# mcat-4cu-v2.net
KiCad netlist of a schematic drawn in EAGLE
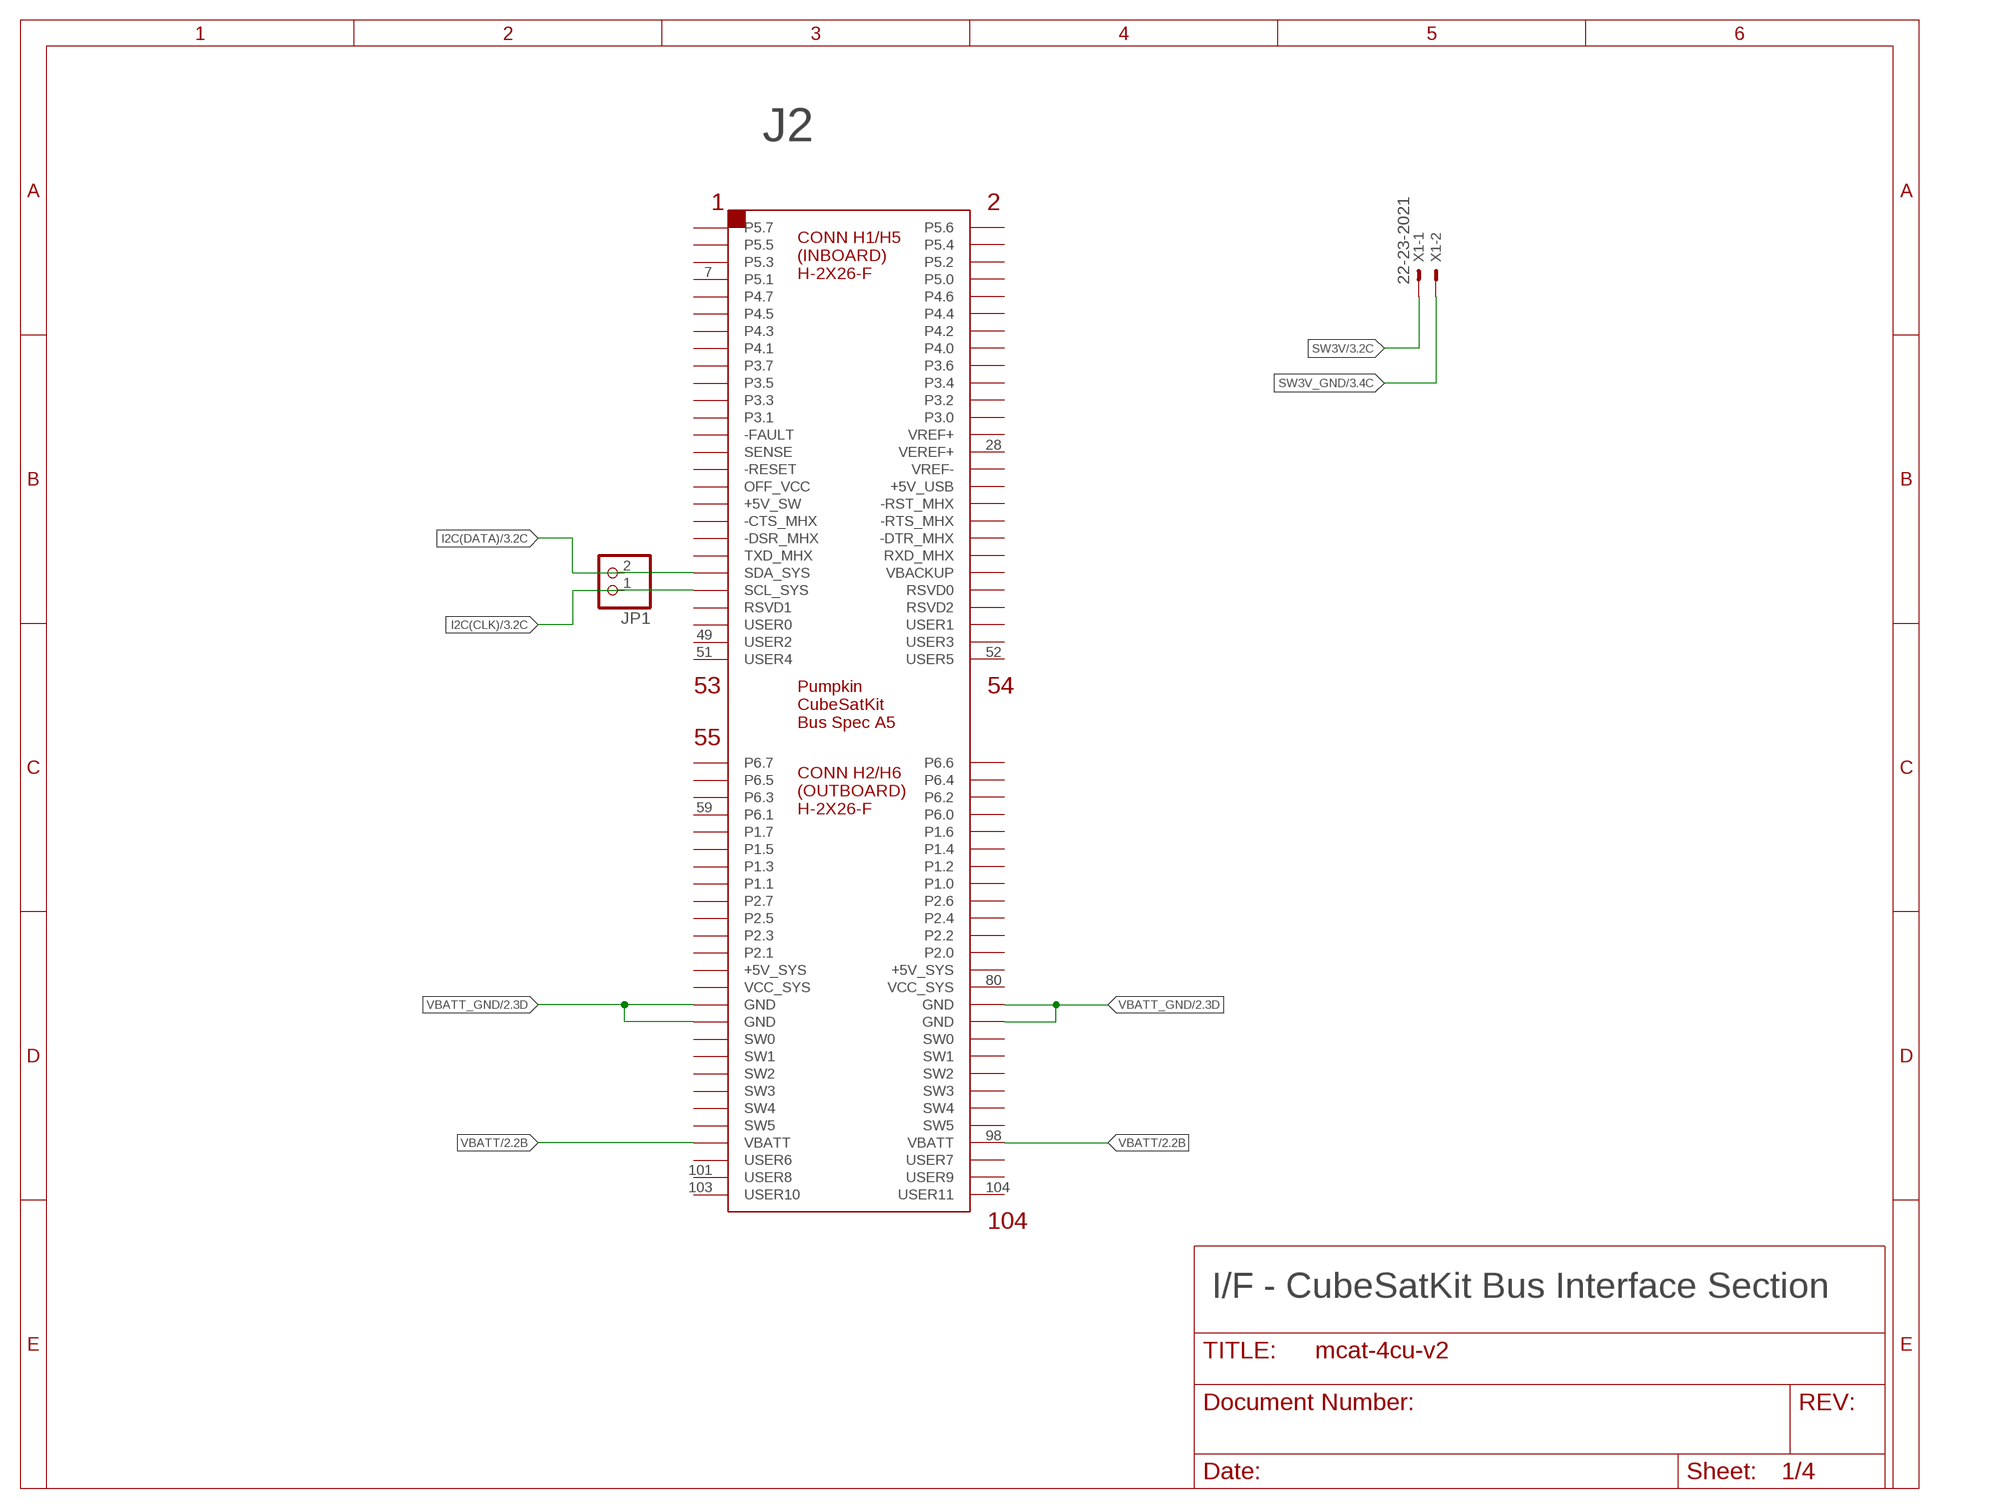
[diagram p0: schematic, sheet 1]
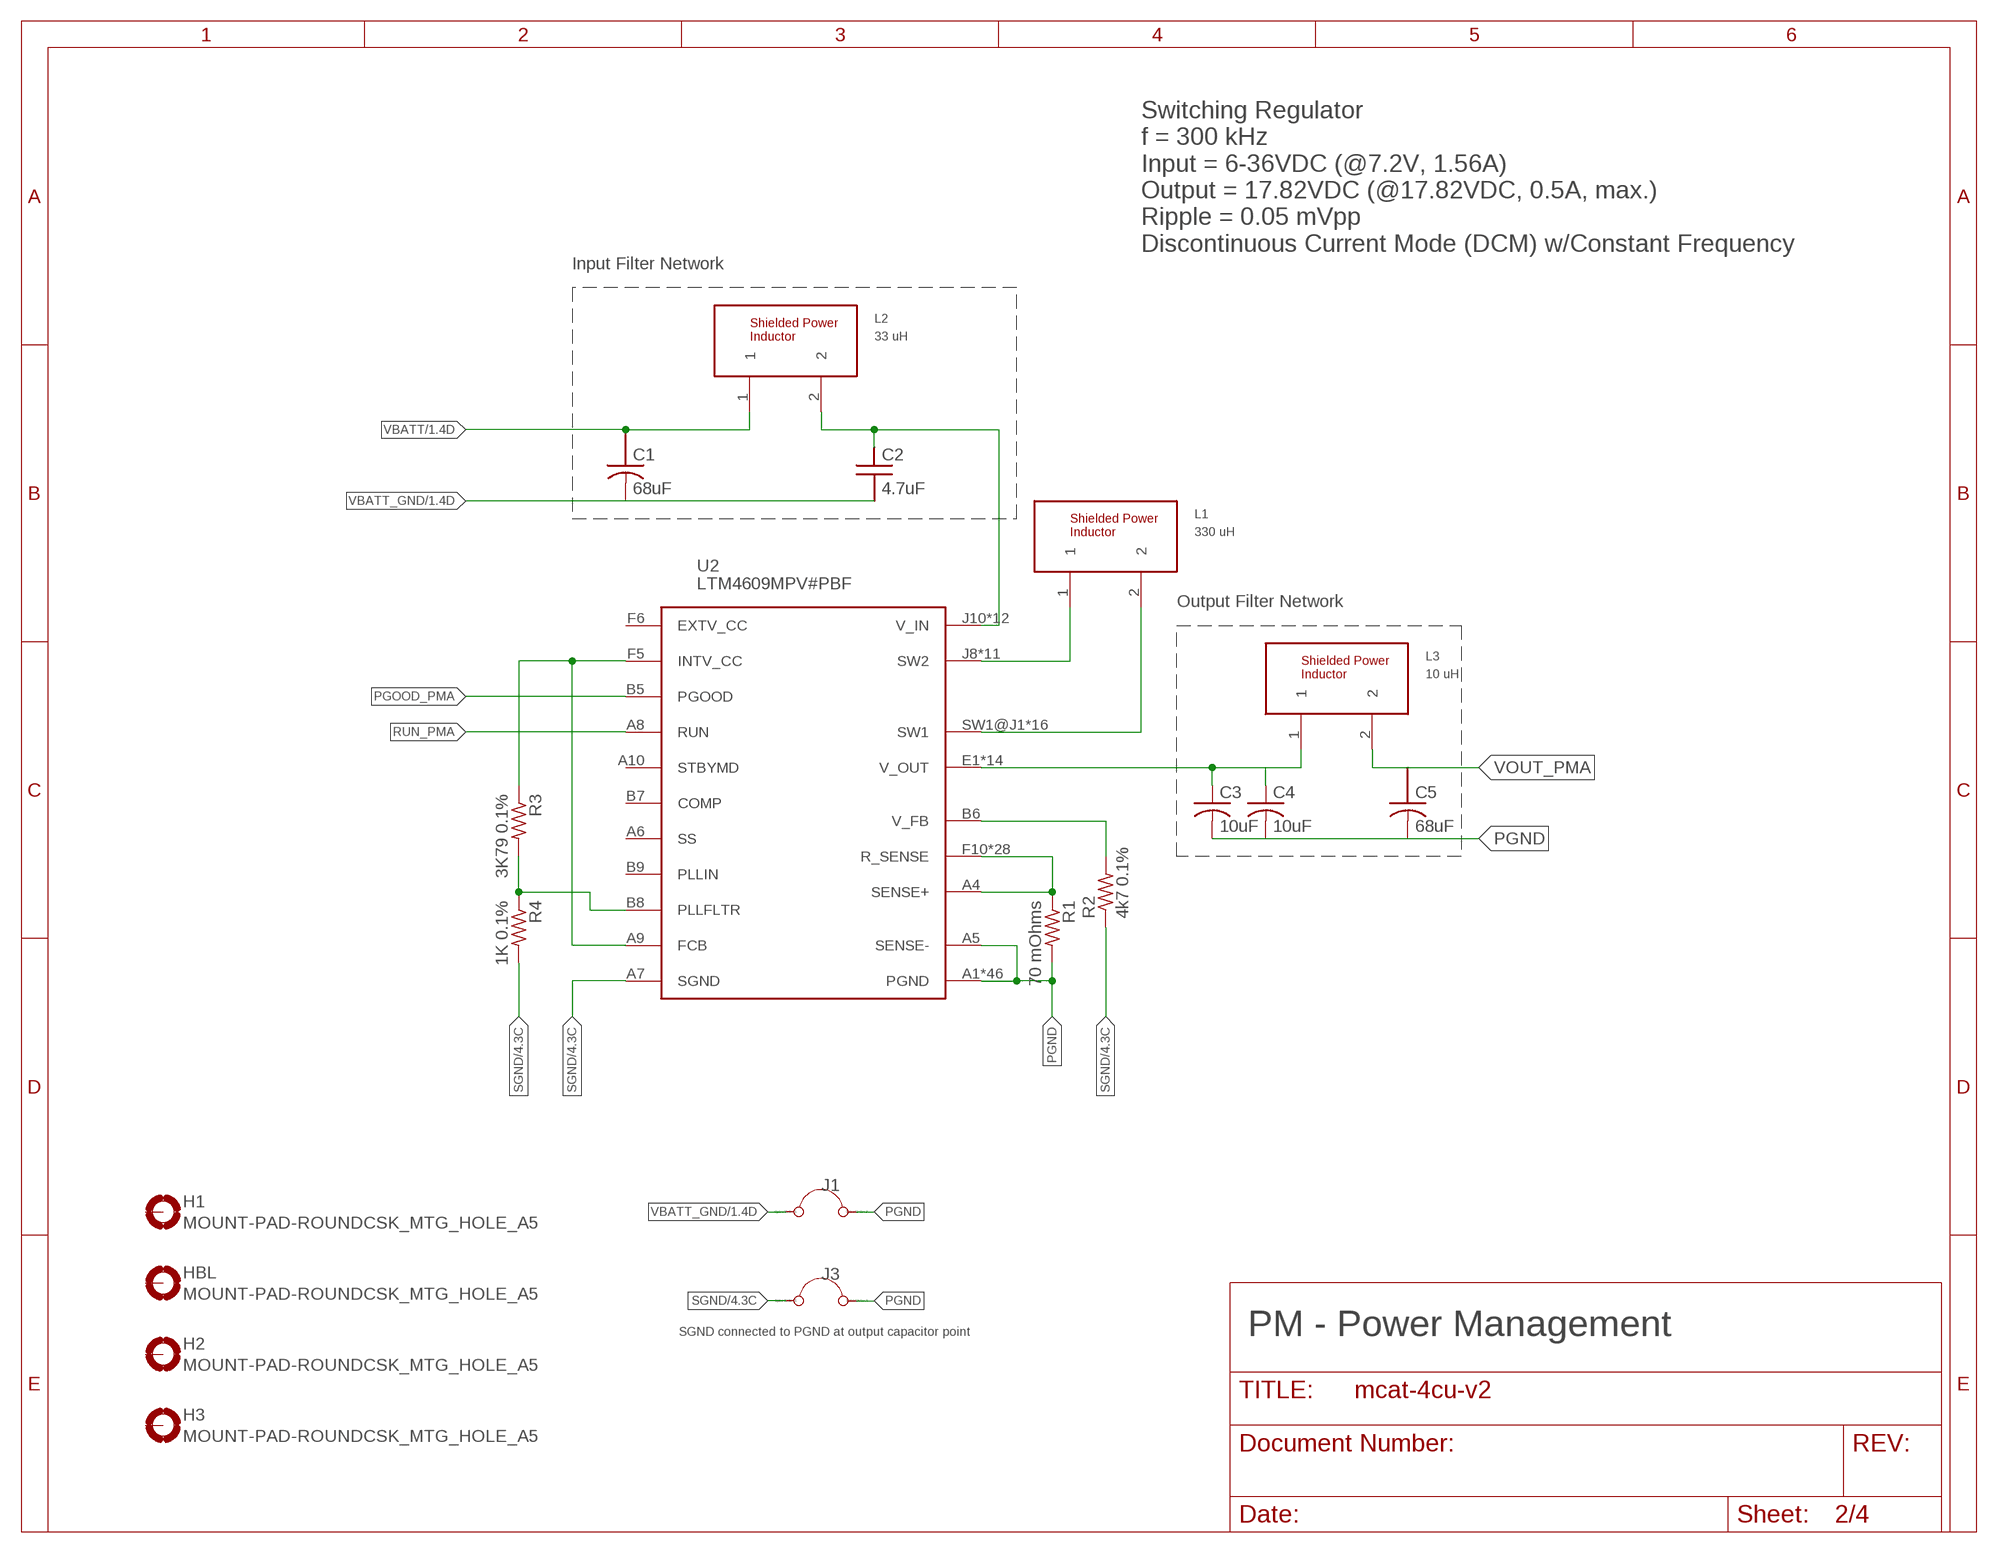
[diagram p1: schematic, sheet 2]
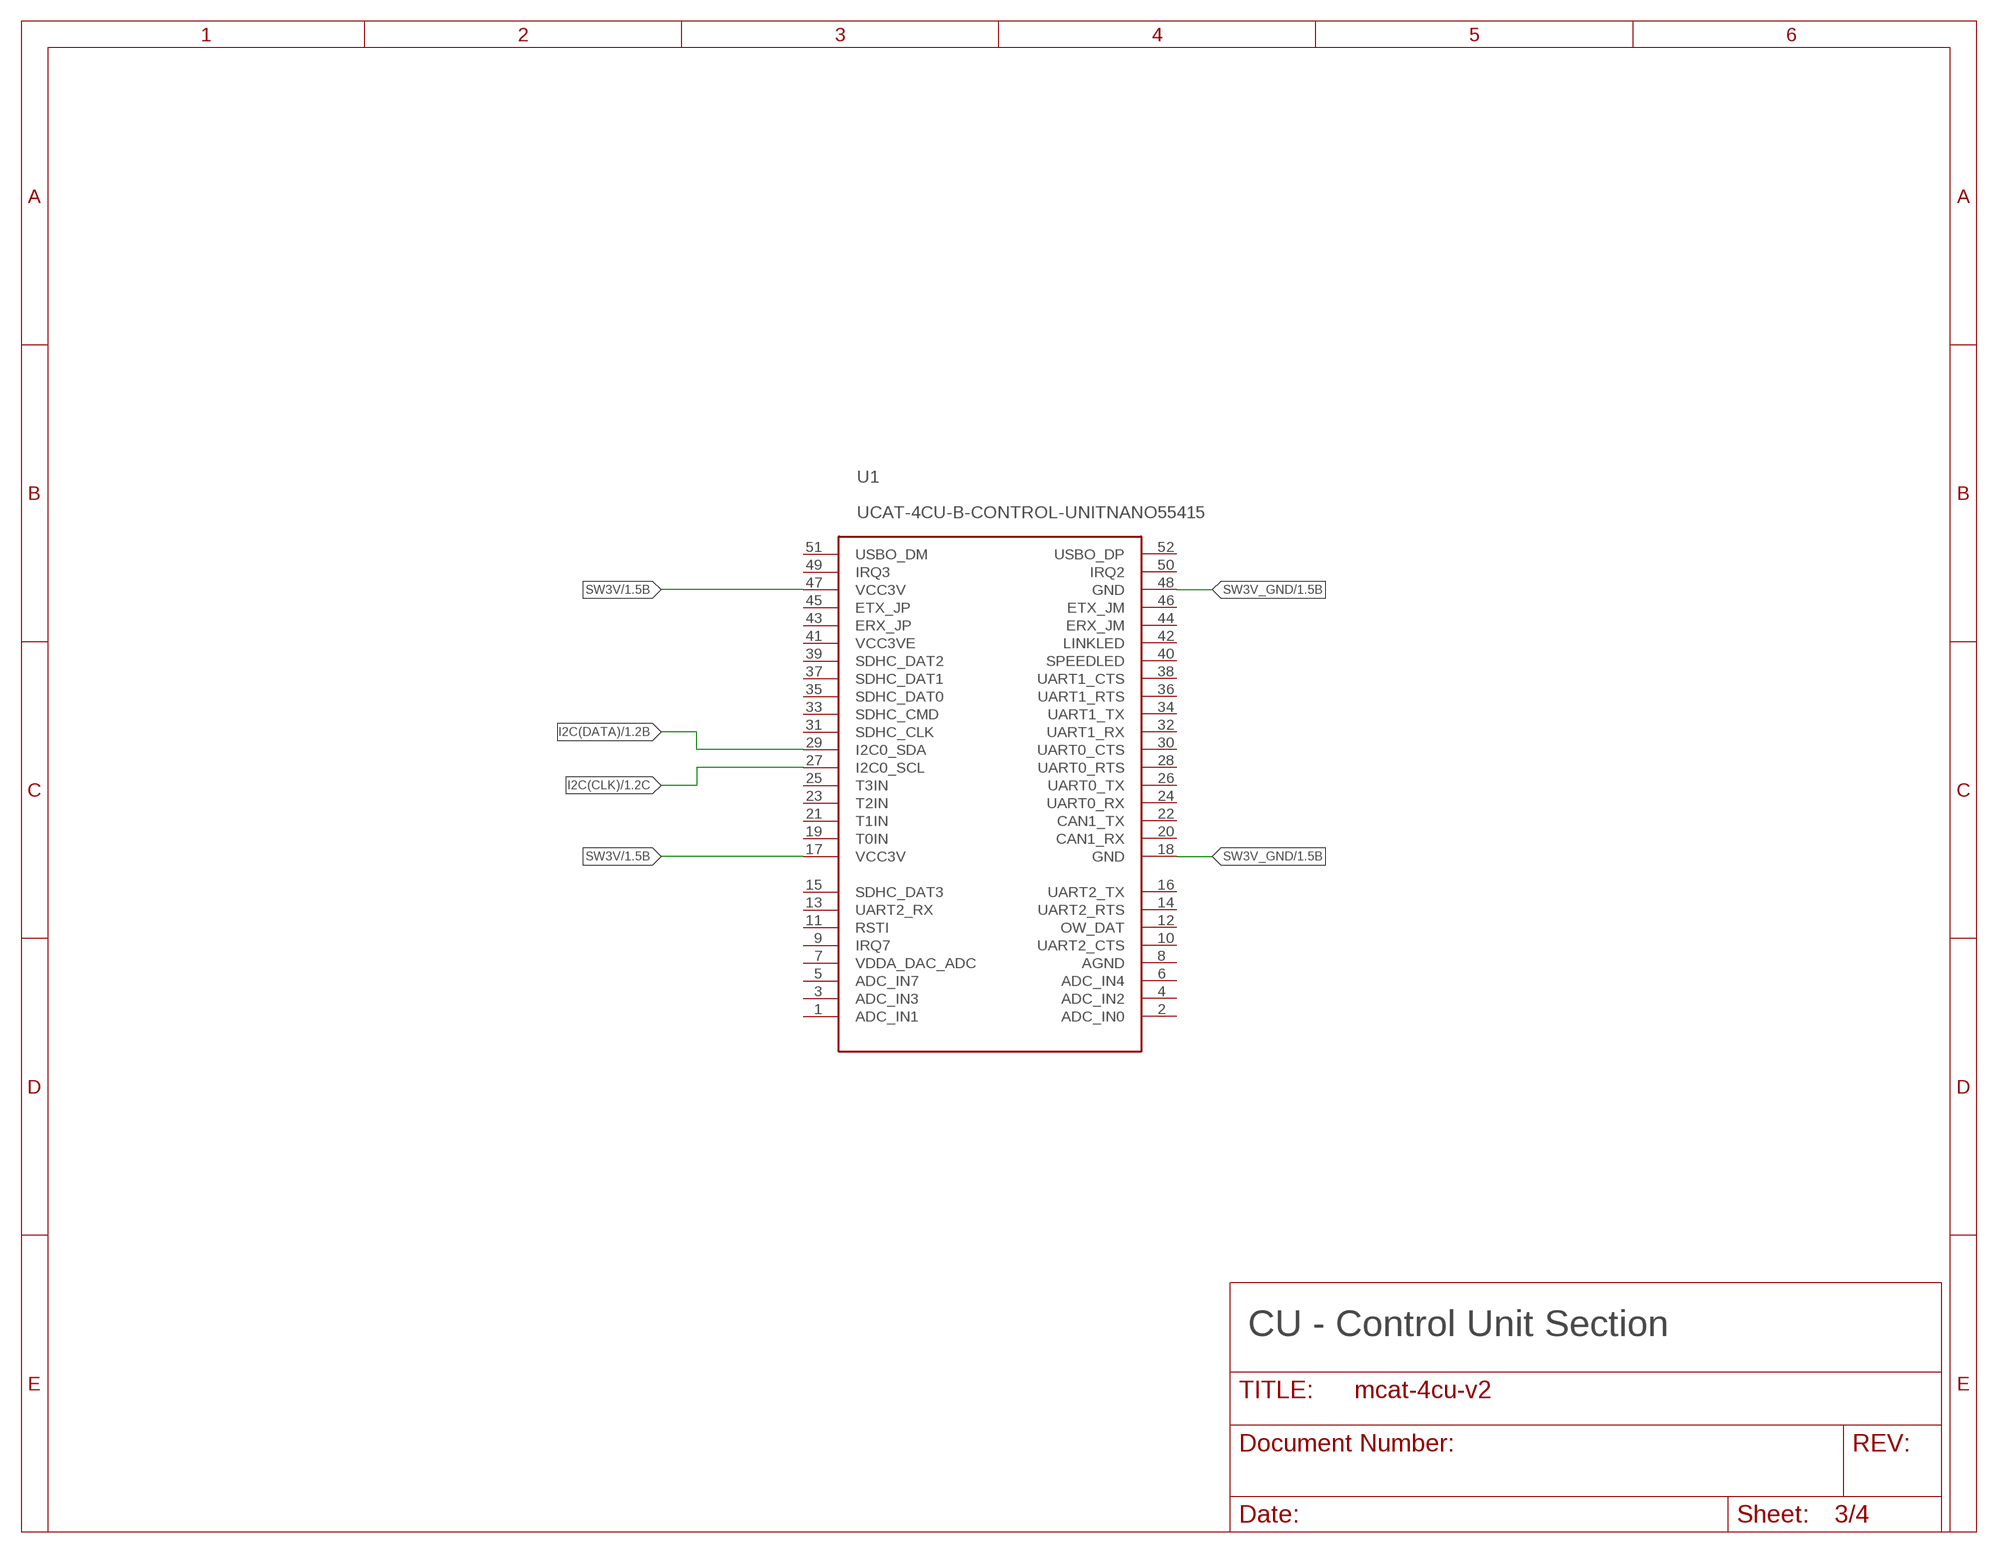
[diagram p2: schematic, sheet 3]
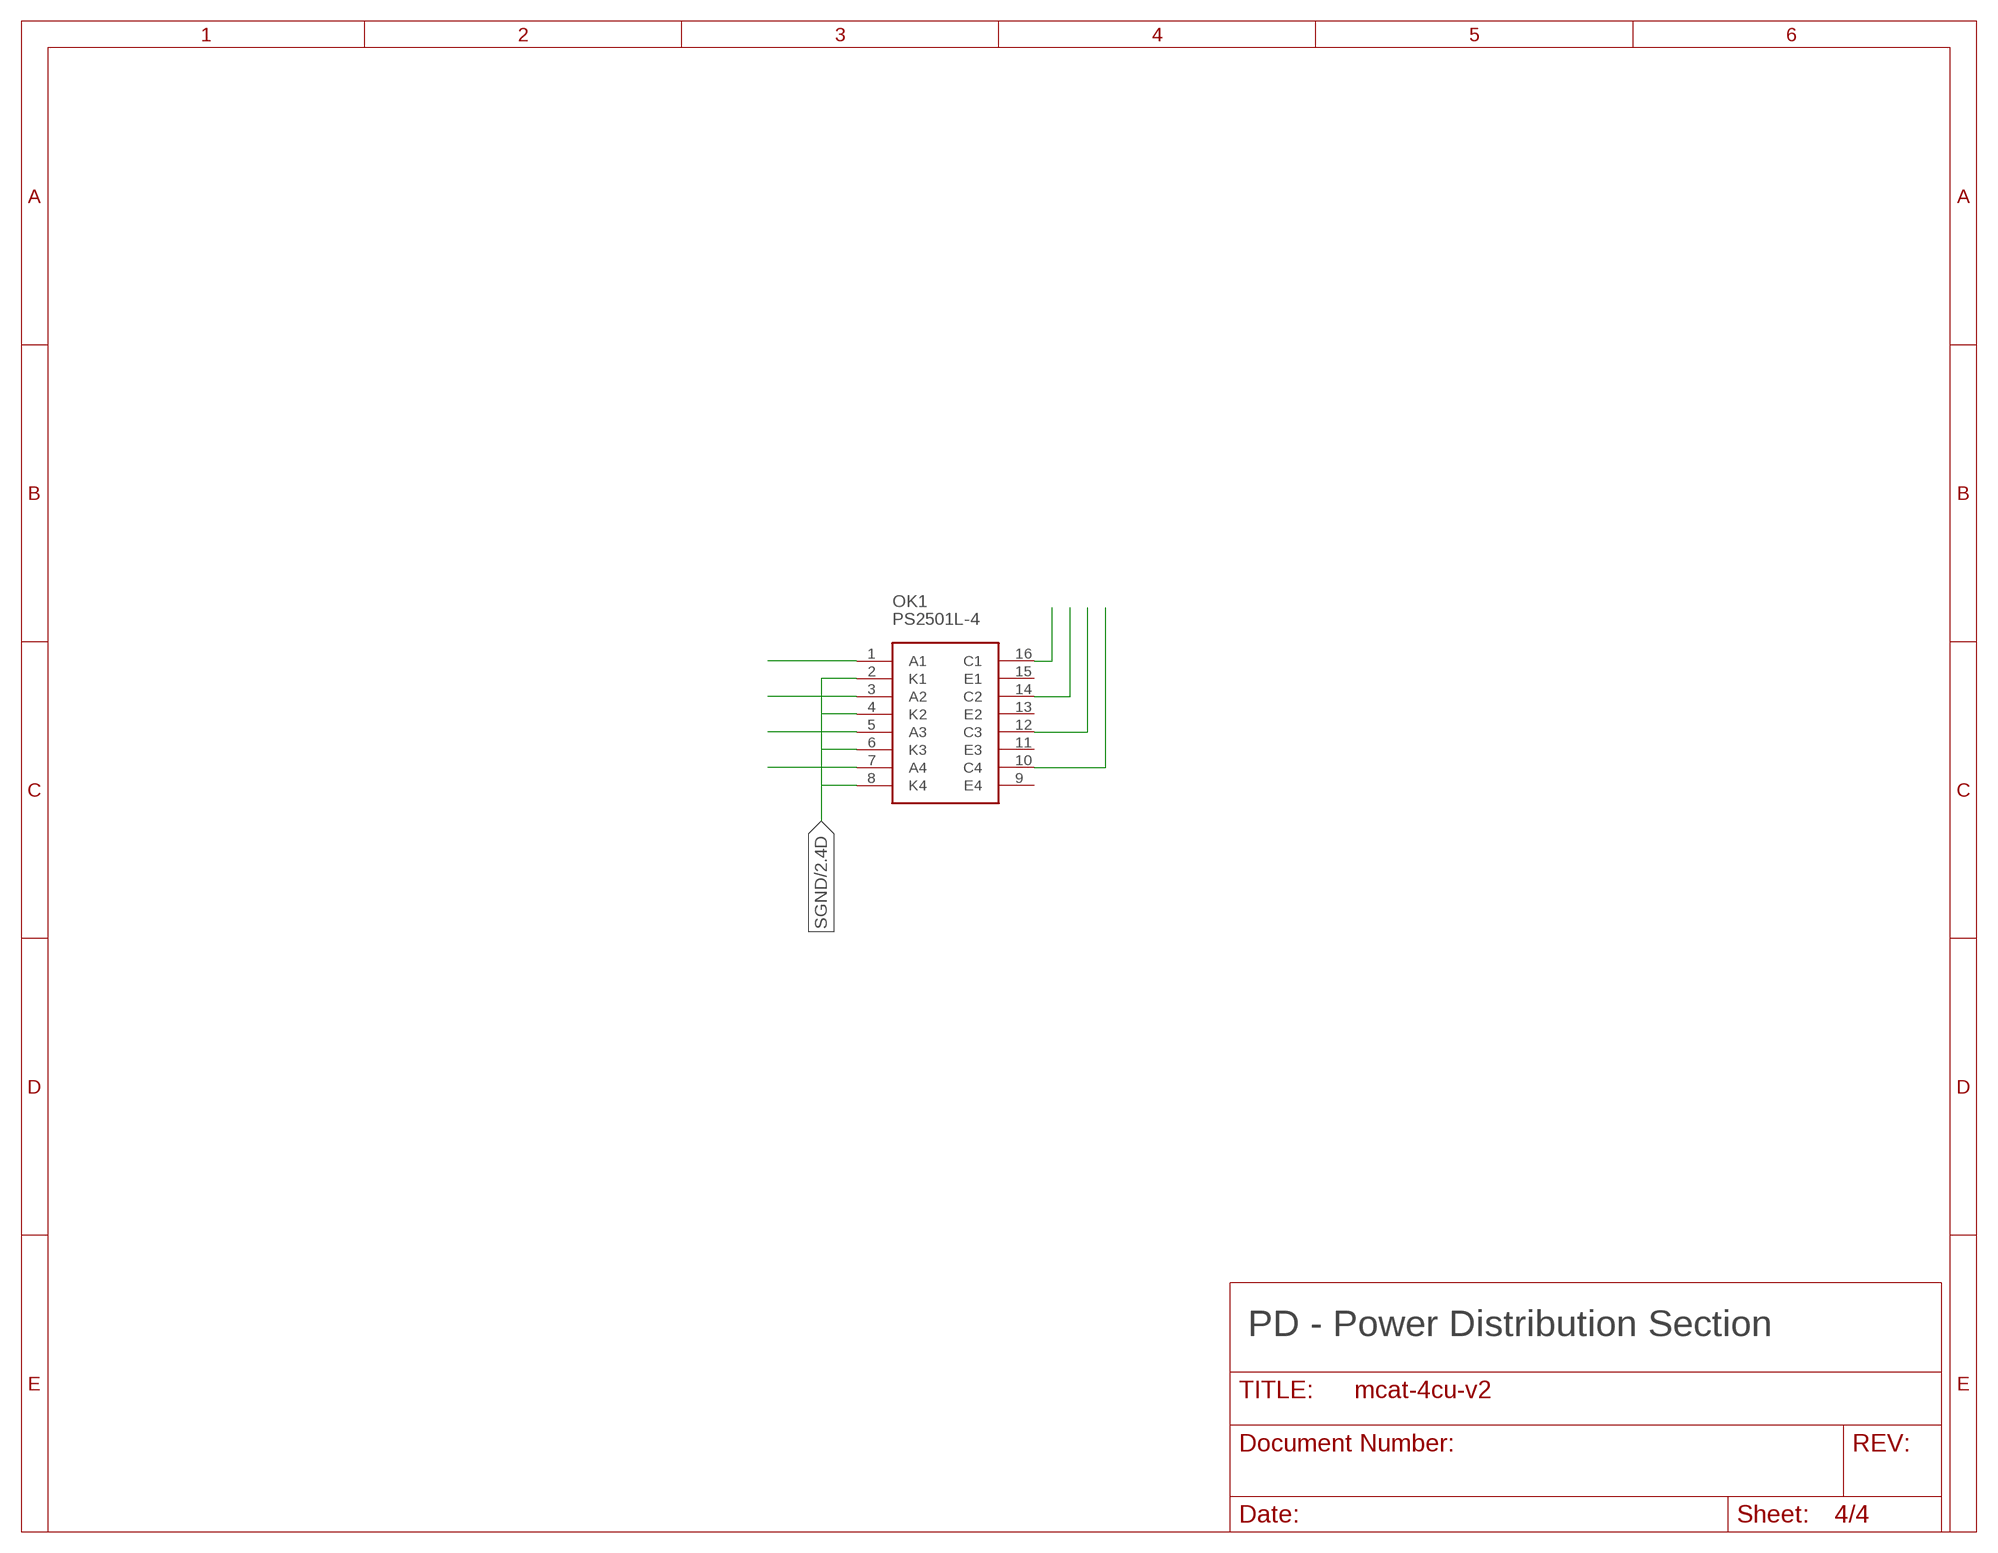
[diagram p3: schematic, sheet 4]

(export (version "E")
  (design (tool "Eeschema 10.0.6"))
  (components
    (comp (ref "J2")
      (value "CSK-BUS-CONN2X2X26")
      (footprint "eagle-import:CSK-BUS-PKG")
      (libsource (lib "eagle-import") (part "CSK-BUS-CONN2X2X26"))
    )
    (comp (ref "JP1")
      (value "PINHD-1X2")
      (footprint "eagle-import:1X02")
      (libsource (lib "eagle-import") (part "PINHD-1X2"))
    )
    (comp (ref "X1")
      (value "22-23-2021")
      (footprint "eagle-import:22-23-2021")
      (fields (field (name "MF") "MOLEX"))
      (libsource (lib "eagle-import") (part "22-23-2021"))
    )
    (comp (ref "OK1")
      (value "PS2501L-4")
      (footprint "eagle-import:PS2501L-4")
      (libsource (lib "eagle-import") (part "PS2501L-4"))
    )
    (comp (ref "C1")
      (value "68uF")
      (footprint "eagle-import:OS-CON-SVPF-F12")
      (libsource (lib "eagle-import") (part "OSCON-50SVPF68M"))
    )
    (comp (ref "C2")
      (value "4.7uF")
      (footprint "eagle-import:MLCC-X7R-1210")
      (libsource (lib "eagle-import") (part "AVX-LD105C475KAB2A"))
    )
    (comp (ref "C3")
      (value "10uF")
      (footprint "eagle-import:C1210K")
      (libsource (lib "eagle-import") (part "C-USC1210K"))
    )
    (comp (ref "C4")
      (value "10uF")
      (footprint "eagle-import:C1210K")
      (libsource (lib "eagle-import") (part "C-USC1210K"))
    )
    (comp (ref "C5")
      (value "68uF")
      (footprint "eagle-import:OS-CON-SVPF-F12")
      (libsource (lib "eagle-import") (part "OSCON-50SVPF68M"))
    )
    (comp (ref "H1")
      (value "MOUNT-PAD-ROUNDCSK_MTG_HOLE_A5")
      (footprint "eagle-import:CSK_MOUNTING_HOLE")
      (libsource (lib "eagle-import") (part "MOUNT-PAD-ROUNDCSK_MTG_HOLE_A5"))
    )
    (comp (ref "H2")
      (value "MOUNT-PAD-ROUNDCSK_MTG_HOLE_A5")
      (footprint "eagle-import:CSK_MOUNTING_HOLE")
      (libsource (lib "eagle-import") (part "MOUNT-PAD-ROUNDCSK_MTG_HOLE_A5"))
    )
    (comp (ref "H3")
      (value "MOUNT-PAD-ROUNDCSK_MTG_HOLE_A5")
      (footprint "eagle-import:CSK_MOUNTING_HOLE")
      (libsource (lib "eagle-import") (part "MOUNT-PAD-ROUNDCSK_MTG_HOLE_A5"))
    )
    (comp (ref "HBL")
      (value "MOUNT-PAD-ROUNDCSK_MTG_HOLE_A5")
      (footprint "eagle-import:CSK_MOUNTING_HOLE")
      (libsource (lib "eagle-import") (part "MOUNT-PAD-ROUNDCSK_MTG_HOLE_A5"))
    )
    (comp (ref "J1")
      (value "JUMPER")
      (footprint "eagle-import:05")
      (libsource (lib "eagle-import") (part "JUMPER"))
    )
    (comp (ref "J3")
      (value "JUMPER")
      (footprint "eagle-import:05")
      (libsource (lib "eagle-import") (part "JUMPER"))
    )
    (comp (ref "L1")
      (value "330 uH")
      (footprint "eagle-import:MSS1048")
      (libsource (lib "eagle-import") (part "MSS1048-334KL_"))
    )
    (comp (ref "L2")
      (value "33 uH")
      (footprint "eagle-import:MSS1048")
      (libsource (lib "eagle-import") (part "MSS1038-333ML_"))
    )
    (comp (ref "L3")
      (value "10 uH")
      (footprint "eagle-import:SERIES-POWER-INDUCTORS")
      (fields (field (name "MF") "PANASONIC") (field (name "MPN") "ELL5PS100M"))
      (libsource (lib "eagle-import") (part "ELL-5PS100M"))
    )
    (comp (ref "R1")
      (value "70 mOhms")
      (footprint "eagle-import:R1206")
      (libsource (lib "eagle-import") (part "resistor_R-US_R1206"))
    )
    (comp (ref "R2")
      (value "4k7 0.1%")
      (footprint "eagle-import:R0603")
      (libsource (lib "eagle-import") (part "resistor_R-US_R0603"))
    )
    (comp (ref "R3")
      (value "3K79 0.1%")
      (footprint "eagle-import:R0805")
      (libsource (lib "eagle-import") (part "R-US_R0805"))
    )
    (comp (ref "R4")
      (value "1K 0.1%")
      (footprint "eagle-import:R0805")
      (libsource (lib "eagle-import") (part "R-US_R0805"))
    )
    (comp (ref "U2")
      (value "LTM4609MPV#PBF")
      (footprint "eagle-import:LGA-141-LTC-05-08-1840-B")
      (libsource (lib "eagle-import") (part "LTM4609MPV#PBFROHS/HITEMP"))
    )
    (comp (ref "U1")
      (value "UCAT-4CU-B-CONTROL-UNITNANO55415")
      (footprint "eagle-import:MOLEX-MINI-PCI-EXPRESS-8MM-52CKT")
      (libsource (lib "eagle-import") (part "UCAT-4CU-B-CONTROL-UNITNANO55415"))
    )
  )
  (nets
    (net (code "1") (name "I2C(CLK)") (class "Default")
      (node (ref "J2") (pin "43") (pinfunction "SCL_SYS_43") (pintype "bidirectional"))
      (node (ref "JP1") (pin "1") (pinfunction "1_1") (pintype "passive"))
      (node (ref "U1") (pin "27") (pinfunction "I2C0_SCL_27") (pintype "bidirectional"))
    )
    (net (code "2") (name "I2C(DATA)") (class "Default")
      (node (ref "J2") (pin "41") (pinfunction "SDA_SYS_41") (pintype "bidirectional"))
      (node (ref "JP1") (pin "2") (pinfunction "2_2") (pintype "passive"))
      (node (ref "U1") (pin "29") (pinfunction "I2C0_SDA_29") (pintype "bidirectional"))
    )
    (net (code "3") (name "Net-(C2-Pad1)") (class "Default")
      (node (ref "C2") (pin "1") (pinfunction "1_1") (pintype "passive"))
      (node (ref "L2") (pin "2") (pinfunction "2_2") (pintype "bidirectional"))
      (node (ref "U2") (pin "J10") (pinfunction "V_IN_J10") (pintype "bidirectional"))
      (node (ref "U2") (pin "J11") (pinfunction "V_IN_J11") (pintype "bidirectional"))
      (node (ref "U2") (pin "J12") (pinfunction "V_IN_J12") (pintype "bidirectional"))
      (node (ref "U2") (pin "K10") (pinfunction "V_IN_K10") (pintype "bidirectional"))
      (node (ref "U2") (pin "K11") (pinfunction "V_IN_K11") (pintype "bidirectional"))
      (node (ref "U2") (pin "K12") (pinfunction "V_IN_K12") (pintype "bidirectional"))
      (node (ref "U2") (pin "L10") (pinfunction "V_IN_L10") (pintype "bidirectional"))
      (node (ref "U2") (pin "L11") (pinfunction "V_IN_L11") (pintype "bidirectional"))
      (node (ref "U2") (pin "L12") (pinfunction "V_IN_L12") (pintype "bidirectional"))
      (node (ref "U2") (pin "M10") (pinfunction "V_IN_M10") (pintype "bidirectional"))
      (node (ref "U2") (pin "M11") (pinfunction "V_IN_M11") (pintype "bidirectional"))
      (node (ref "U2") (pin "M12") (pinfunction "V_IN_M12") (pintype "bidirectional"))
    )
    (net (code "4") (name "Net-(C3-Pad1)") (class "Default")
      (node (ref "C3") (pin "1") (pinfunction "1_1") (pintype "passive"))
      (node (ref "C4") (pin "1") (pinfunction "1_1") (pintype "passive"))
      (node (ref "L3") (pin "1") (pinfunction "1_1") (pintype "bidirectional"))
      (node (ref "U2") (pin "E1") (pinfunction "V_OUT_E1") (pintype "bidirectional"))
      (node (ref "U2") (pin "E2") (pinfunction "V_OUT_E2") (pintype "bidirectional"))
      (node (ref "U2") (pin "F1") (pinfunction "V_OUT_F1") (pintype "bidirectional"))
      (node (ref "U2") (pin "F2") (pinfunction "V_OUT_F2") (pintype "bidirectional"))
      (node (ref "U2") (pin "F3") (pinfunction "V_OUT_F3") (pintype "bidirectional"))
      (node (ref "U2") (pin "F4") (pinfunction "V_OUT_F4") (pintype "bidirectional"))
      (node (ref "U2") (pin "G1") (pinfunction "V_OUT_G1") (pintype "bidirectional"))
      (node (ref "U2") (pin "G2") (pinfunction "V_OUT_G2") (pintype "bidirectional"))
      (node (ref "U2") (pin "G3") (pinfunction "V_OUT_G3") (pintype "bidirectional"))
      (node (ref "U2") (pin "G4") (pinfunction "V_OUT_G4") (pintype "bidirectional"))
      (node (ref "U2") (pin "H2") (pinfunction "V_OUT_H2") (pintype "bidirectional"))
      (node (ref "U2") (pin "H3") (pinfunction "V_OUT_H3") (pintype "bidirectional"))
      (node (ref "U2") (pin "H4") (pinfunction "V_OUT_H4") (pintype "bidirectional"))
      (node (ref "U2") (pin "VOUT") (pinfunction "V_OUT_VOUT") (pintype "bidirectional"))
    )
    (net (code "5") (name "Net-(J2-GND-Pad82)") (class "Default")
      (node (ref "J2") (pin "82") (pinfunction "GND_82") (pintype "bidirectional"))
      (node (ref "J2") (pin "84") (pinfunction "GND_84") (pintype "bidirectional"))
    )
    (net (code "6") (name "Net-(L1-Pad1)") (class "Default")
      (node (ref "L1") (pin "1") (pinfunction "1_1") (pintype "bidirectional"))
      (node (ref "U2") (pin "J8") (pinfunction "SW2_J8") (pintype "bidirectional"))
      (node (ref "U2") (pin "J9") (pinfunction "SW2_J9") (pintype "bidirectional"))
      (node (ref "U2") (pin "K7") (pinfunction "SW2_K7") (pintype "bidirectional"))
      (node (ref "U2") (pin "K8") (pinfunction "SW2_K8") (pintype "bidirectional"))
      (node (ref "U2") (pin "K9") (pinfunction "SW2_K9") (pintype "bidirectional"))
      (node (ref "U2") (pin "L7") (pinfunction "SW2_L7") (pintype "bidirectional"))
      (node (ref "U2") (pin "L8") (pinfunction "SW2_L8") (pintype "bidirectional"))
      (node (ref "U2") (pin "L9") (pinfunction "SW2_L9") (pintype "bidirectional"))
      (node (ref "U2") (pin "M7") (pinfunction "SW2_M7") (pintype "bidirectional"))
      (node (ref "U2") (pin "M8") (pinfunction "SW2_M8") (pintype "bidirectional"))
      (node (ref "U2") (pin "M9") (pinfunction "SW2_M9") (pintype "bidirectional"))
    )
    (net (code "7") (name "Net-(L1-Pad2)") (class "Default")
      (node (ref "L1") (pin "2") (pinfunction "2_2") (pintype "bidirectional"))
      (node (ref "U2") (pin "SW1@J1") (pinfunction "SW1_SW1@J1") (pintype "bidirectional"))
      (node (ref "U2") (pin "SW1@J2") (pinfunction "SW1_SW1@J2") (pintype "bidirectional"))
      (node (ref "U2") (pin "SW1@J3") (pinfunction "SW1_SW1@J3") (pintype "bidirectional"))
      (node (ref "U2") (pin "SW1@J4") (pinfunction "SW1_SW1@J4") (pintype "bidirectional"))
      (node (ref "U2") (pin "SW1@K1") (pinfunction "SW1_SW1@K1") (pintype "bidirectional"))
      (node (ref "U2") (pin "SW1@K2") (pinfunction "SW1_SW1@K2") (pintype "bidirectional"))
      (node (ref "U2") (pin "SW1@K3") (pinfunction "SW1_SW1@K3") (pintype "bidirectional"))
      (node (ref "U2") (pin "SW1@K4") (pinfunction "SW1_SW1@K4") (pintype "bidirectional"))
      (node (ref "U2") (pin "SW1@L1") (pinfunction "SW1_SW1@L1") (pintype "bidirectional"))
      (node (ref "U2") (pin "SW1@L2") (pinfunction "SW1_SW1@L2") (pintype "bidirectional"))
      (node (ref "U2") (pin "SW1@L3") (pinfunction "SW1_SW1@L3") (pintype "bidirectional"))
      (node (ref "U2") (pin "SW1@L4") (pinfunction "SW1_SW1@L4") (pintype "bidirectional"))
      (node (ref "U2") (pin "SW1@M1") (pinfunction "SW1_SW1@M1") (pintype "bidirectional"))
      (node (ref "U2") (pin "SW1@M2") (pinfunction "SW1_SW1@M2") (pintype "bidirectional"))
      (node (ref "U2") (pin "SW1@M3") (pinfunction "SW1_SW1@M3") (pintype "bidirectional"))
      (node (ref "U2") (pin "SW1@M4") (pinfunction "SW1_SW1@M4") (pintype "bidirectional"))
    )
    (net (code "8") (name "Net-(U2-FCB)") (class "Default")
      (node (ref "R3") (pin "1") (pinfunction "1_1") (pintype "passive"))
      (node (ref "U2") (pin "A9") (pinfunction "FCB_A9") (pintype "bidirectional"))
      (node (ref "U2") (pin "F5") (pinfunction "INTV_CC_F5") (pintype "bidirectional"))
    )
    (net (code "9") (name "Net-(U2-PLLFLTR)") (class "Default")
      (node (ref "R3") (pin "2") (pinfunction "2_2") (pintype "passive"))
      (node (ref "R4") (pin "1") (pinfunction "1_1") (pintype "passive"))
      (node (ref "U2") (pin "B8") (pinfunction "PLLFLTR_B8") (pintype "bidirectional"))
    )
    (net (code "10") (name "Net-(U2-SENSE+)") (class "Default")
      (node (ref "R1") (pin "1") (pinfunction "1_1") (pintype "passive"))
      (node (ref "U2") (pin "A4") (pinfunction "SENSE+_A4") (pintype "bidirectional"))
      (node (ref "U2") (pin "F10") (pinfunction "R_SENSE_F10") (pintype "bidirectional"))
      (node (ref "U2") (pin "F11") (pinfunction "R_SENSE_F11") (pintype "bidirectional"))
      (node (ref "U2") (pin "F12") (pinfunction "R_SENSE_F12") (pintype "bidirectional"))
      (node (ref "U2") (pin "G10") (pinfunction "R_SENSE_G10") (pintype "bidirectional"))
      (node (ref "U2") (pin "G11") (pinfunction "R_SENSE_G11") (pintype "bidirectional"))
      (node (ref "U2") (pin "G12") (pinfunction "R_SENSE_G12") (pintype "bidirectional"))
      (node (ref "U2") (pin "G5") (pinfunction "R_SENSE_G5") (pintype "bidirectional"))
      (node (ref "U2") (pin "G6") (pinfunction "R_SENSE_G6") (pintype "bidirectional"))
      (node (ref "U2") (pin "G7") (pinfunction "R_SENSE_G7") (pintype "bidirectional"))
      (node (ref "U2") (pin "G8") (pinfunction "R_SENSE_G8") (pintype "bidirectional"))
      (node (ref "U2") (pin "G9") (pinfunction "R_SENSE_G9") (pintype "bidirectional"))
      (node (ref "U2") (pin "H10") (pinfunction "R_SENSE_H10") (pintype "bidirectional"))
      (node (ref "U2") (pin "H11") (pinfunction "R_SENSE_H11") (pintype "bidirectional"))
      (node (ref "U2") (pin "H12") (pinfunction "R_SENSE_H12") (pintype "bidirectional"))
      (node (ref "U2") (pin "H5") (pinfunction "R_SENSE_H5") (pintype "bidirectional"))
      (node (ref "U2") (pin "H6") (pinfunction "R_SENSE_H6") (pintype "bidirectional"))
      (node (ref "U2") (pin "H7") (pinfunction "R_SENSE_H7") (pintype "bidirectional"))
      (node (ref "U2") (pin "H8") (pinfunction "R_SENSE_H8") (pintype "bidirectional"))
      (node (ref "U2") (pin "H9") (pinfunction "R_SENSE_H9") (pintype "bidirectional"))
      (node (ref "U2") (pin "J5") (pinfunction "R_SENSE_J5") (pintype "bidirectional"))
      (node (ref "U2") (pin "J6") (pinfunction "R_SENSE_J6") (pintype "bidirectional"))
      (node (ref "U2") (pin "J7") (pinfunction "R_SENSE_J7") (pintype "bidirectional"))
      (node (ref "U2") (pin "K5") (pinfunction "R_SENSE_K5") (pintype "bidirectional"))
      (node (ref "U2") (pin "K6") (pinfunction "R_SENSE_K6") (pintype "bidirectional"))
      (node (ref "U2") (pin "L5") (pinfunction "R_SENSE_L5") (pintype "bidirectional"))
      (node (ref "U2") (pin "L6") (pinfunction "R_SENSE_L6") (pintype "bidirectional"))
      (node (ref "U2") (pin "M5") (pinfunction "R_SENSE_M5") (pintype "bidirectional"))
      (node (ref "U2") (pin "M6") (pinfunction "R_SENSE_M6") (pintype "bidirectional"))
    )
    (net (code "11") (name "Net-(U2-V_FB)") (class "Default")
      (node (ref "R2") (pin "2") (pinfunction "2_2") (pintype "passive"))
      (node (ref "U2") (pin "B6") (pinfunction "V_FB_B6") (pintype "bidirectional"))
    )
    (net (code "12") (name "PGND") (class "Default")
      (node (ref "C3") (pin "2") (pinfunction "2_2") (pintype "passive"))
      (node (ref "C4") (pin "2") (pinfunction "2_2") (pintype "passive"))
      (node (ref "C5") (pin "K1") (pinfunction "K_K1") (pintype "passive"))
      (node (ref "J1") (pin "2") (pinfunction "-_2") (pintype "passive"))
      (node (ref "J3") (pin "2") (pinfunction "-_2") (pintype "passive"))
      (node (ref "R1") (pin "2") (pinfunction "2_2") (pintype "passive"))
      (node (ref "U2") (pin "A1") (pinfunction "PGND_A1") (pintype "bidirectional"))
      (node (ref "U2") (pin "A11") (pinfunction "PGND_A11") (pintype "bidirectional"))
      (node (ref "U2") (pin "A12") (pinfunction "PGND_A12") (pintype "bidirectional"))
      (node (ref "U2") (pin "A2") (pinfunction "PGND_A2") (pintype "bidirectional"))
      (node (ref "U2") (pin "A3") (pinfunction "PGND_A3") (pintype "bidirectional"))
      (node (ref "U2") (pin "A5") (pinfunction "SENSE-_A5") (pintype "bidirectional"))
      (node (ref "U2") (pin "B1") (pinfunction "PGND_B1") (pintype "bidirectional"))
      (node (ref "U2") (pin "B10") (pinfunction "PGND_B10") (pintype "bidirectional"))
      (node (ref "U2") (pin "B11") (pinfunction "PGND_B11") (pintype "bidirectional"))
      (node (ref "U2") (pin "B12") (pinfunction "PGND_B12") (pintype "bidirectional"))
      (node (ref "U2") (pin "B2") (pinfunction "PGND_B2") (pintype "bidirectional"))
      (node (ref "U2") (pin "B3") (pinfunction "PGND_B3") (pintype "bidirectional"))
      (node (ref "U2") (pin "B4") (pinfunction "PGND_B4") (pintype "bidirectional"))
      (node (ref "U2") (pin "C1") (pinfunction "PGND_C1") (pintype "bidirectional"))
      (node (ref "U2") (pin "C10") (pinfunction "PGND_C10") (pintype "bidirectional"))
      (node (ref "U2") (pin "C11") (pinfunction "PGND_C11") (pintype "bidirectional"))
      (node (ref "U2") (pin "C12") (pinfunction "PGND_C12") (pintype "bidirectional"))
      (node (ref "U2") (pin "C2") (pinfunction "PGND_C2") (pintype "bidirectional"))
      (node (ref "U2") (pin "C3") (pinfunction "PGND_C3") (pintype "bidirectional"))
      (node (ref "U2") (pin "C4") (pinfunction "PGND_C4") (pintype "bidirectional"))
      (node (ref "U2") (pin "C5") (pinfunction "PGND_C5") (pintype "bidirectional"))
      (node (ref "U2") (pin "C6") (pinfunction "PGND_C6") (pintype "bidirectional"))
      (node (ref "U2") (pin "C7") (pinfunction "PGND_C7") (pintype "bidirectional"))
      (node (ref "U2") (pin "C8") (pinfunction "PGND_C8") (pintype "bidirectional"))
      (node (ref "U2") (pin "C9") (pinfunction "PGND_C9") (pintype "bidirectional"))
      (node (ref "U2") (pin "D1") (pinfunction "PGND_D1") (pintype "bidirectional"))
      (node (ref "U2") (pin "D10") (pinfunction "PGND_D10") (pintype "bidirectional"))
      (node (ref "U2") (pin "D11") (pinfunction "PGND_D11") (pintype "bidirectional"))
      (node (ref "U2") (pin "D12") (pinfunction "PGND_D12") (pintype "bidirectional"))
      (node (ref "U2") (pin "D2") (pinfunction "PGND_D2") (pintype "bidirectional"))
      (node (ref "U2") (pin "D3") (pinfunction "PGND_D3") (pintype "bidirectional"))
      (node (ref "U2") (pin "D4") (pinfunction "PGND_D4") (pintype "bidirectional"))
      (node (ref "U2") (pin "D5") (pinfunction "PGND_D5") (pintype "bidirectional"))
      (node (ref "U2") (pin "D6") (pinfunction "PGND_D6") (pintype "bidirectional"))
      (node (ref "U2") (pin "D7") (pinfunction "PGND_D7") (pintype "bidirectional"))
      (node (ref "U2") (pin "D8") (pinfunction "PGND_D8") (pintype "bidirectional"))
      (node (ref "U2") (pin "D9") (pinfunction "PGND_D9") (pintype "bidirectional"))
      (node (ref "U2") (pin "E10") (pinfunction "PGND_E10") (pintype "bidirectional"))
      (node (ref "U2") (pin "E11") (pinfunction "PGND_E11") (pintype "bidirectional"))
      (node (ref "U2") (pin "E12") (pinfunction "PGND_E12") (pintype "bidirectional"))
      (node (ref "U2") (pin "E3") (pinfunction "PGND_E3") (pintype "bidirectional"))
      (node (ref "U2") (pin "E4") (pinfunction "PGND_E4") (pintype "bidirectional"))
      (node (ref "U2") (pin "E5") (pinfunction "PGND_E5") (pintype "bidirectional"))
      (node (ref "U2") (pin "E6") (pinfunction "PGND_E6") (pintype "bidirectional"))
      (node (ref "U2") (pin "E7") (pinfunction "PGND_E7") (pintype "bidirectional"))
      (node (ref "U2") (pin "E8") (pinfunction "PGND_E8") (pintype "bidirectional"))
      (node (ref "U2") (pin "E9") (pinfunction "PGND_E9") (pintype "bidirectional"))
    )
    (net (code "13") (name "PGOOD_PMA") (class "Default")
      (node (ref "U2") (pin "B5") (pinfunction "PGOOD_B5") (pintype "bidirectional"))
    )
    (net (code "14") (name "RUN_PMA") (class "Default")
      (node (ref "U2") (pin "A8") (pinfunction "RUN_A8") (pintype "bidirectional"))
    )
    (net (code "15") (name "SGND") (class "Default")
      (node (ref "J3") (pin "1") (pinfunction "+_1") (pintype "passive"))
      (node (ref "OK1") (pin "2") (pinfunction "K1_2") (pintype "bidirectional"))
      (node (ref "OK1") (pin "4") (pinfunction "K2_4") (pintype "bidirectional"))
      (node (ref "OK1") (pin "6") (pinfunction "K3_6") (pintype "bidirectional"))
      (node (ref "OK1") (pin "8") (pinfunction "K4_8") (pintype "bidirectional"))
      (node (ref "R2") (pin "1") (pinfunction "1_1") (pintype "passive"))
      (node (ref "R4") (pin "2") (pinfunction "2_2") (pintype "passive"))
      (node (ref "U2") (pin "A7") (pinfunction "SGND_A7") (pintype "bidirectional"))
    )
    (net (code "16") (name "SW3V") (class "Default")
      (node (ref "U1") (pin "17") (pinfunction "VCC3V_17") (pintype "bidirectional"))
      (node (ref "U1") (pin "47") (pinfunction "VCC3V_47") (pintype "bidirectional"))
      (node (ref "X1") (pin "1") (pinfunction "S_1") (pintype "passive"))
    )
    (net (code "17") (name "SW3V_GND") (class "Default")
      (node (ref "U1") (pin "48") (pinfunction "GND_48") (pintype "bidirectional"))
      (node (ref "X1") (pin "2") (pinfunction "S_2") (pintype "passive"))
    )
    (net (code "18") (name "VBATT") (class "Default")
      (node (ref "C1") (pin "A1") (pinfunction "A_A1") (pintype "passive"))
      (node (ref "J2") (pin "97") (pinfunction "VBATT_97") (pintype "bidirectional"))
      (node (ref "J2") (pin "98") (pinfunction "VBATT_98") (pintype "bidirectional"))
      (node (ref "L2") (pin "1") (pinfunction "1_1") (pintype "bidirectional"))
    )
    (net (code "19") (name "VBATT_GND") (class "Default")
      (node (ref "C1") (pin "K1") (pinfunction "K_K1") (pintype "passive"))
      (node (ref "C2") (pin "2") (pinfunction "2_2") (pintype "passive"))
      (node (ref "J1") (pin "1") (pinfunction "+_1") (pintype "passive"))
      (node (ref "J2") (pin "81") (pinfunction "GND_81") (pintype "bidirectional"))
      (node (ref "J2") (pin "83") (pinfunction "GND_83") (pintype "bidirectional"))
    )
    (net (code "20") (name "VOUT_PMA") (class "Default")
      (node (ref "C5") (pin "A1") (pinfunction "A_A1") (pintype "passive"))
      (node (ref "L3") (pin "2") (pinfunction "2_2") (pintype "bidirectional"))
    )
    (net (code "21") (name "unconnected-(H1-MOUNT-PadP$1)") (class "Default")
      (node (ref "H1") (pin "P$1") (pinfunction "MOUNT_P$1") (pintype "passive"))
    )
    (net (code "22") (name "unconnected-(H2-MOUNT-PadP$1)") (class "Default")
      (node (ref "H2") (pin "P$1") (pinfunction "MOUNT_P$1") (pintype "passive"))
    )
    (net (code "23") (name "unconnected-(H3-MOUNT-PadP$1)") (class "Default")
      (node (ref "H3") (pin "P$1") (pinfunction "MOUNT_P$1") (pintype "passive"))
    )
    (net (code "24") (name "unconnected-(HBL-MOUNT-PadP$1)") (class "Default")
      (node (ref "HBL") (pin "P$1") (pinfunction "MOUNT_P$1") (pintype "passive"))
    )
    (net (code "25") (name "unconnected-(J2-+5V_SW-Pad33)") (class "Default")
      (node (ref "J2") (pin "33") (pinfunction "+5V_SW_33") (pintype "bidirectional"))
    )
    (net (code "26") (name "unconnected-(J2-+5V_SYS-Pad77)") (class "Default")
      (node (ref "J2") (pin "77") (pinfunction "+5V_SYS_77") (pintype "bidirectional"))
    )
    (net (code "27") (name "unconnected-(J2-+5V_SYS-Pad78)") (class "Default")
      (node (ref "J2") (pin "78") (pinfunction "+5V_SYS_78") (pintype "bidirectional"))
    )
    (net (code "28") (name "unconnected-(J2-+5V_USB-Pad32)") (class "Default")
      (node (ref "J2") (pin "32") (pinfunction "+5V_USB_32") (pintype "bidirectional"))
    )
    (net (code "29") (name "unconnected-(J2--CTS_MHX-Pad35)") (class "Default")
      (node (ref "J2") (pin "35") (pinfunction "-CTS_MHX_35") (pintype "bidirectional"))
    )
    (net (code "30") (name "unconnected-(J2--DSR_MHX-Pad37)") (class "Default")
      (node (ref "J2") (pin "37") (pinfunction "-DSR_MHX_37") (pintype "bidirectional"))
    )
    (net (code "31") (name "unconnected-(J2--DTR_MHX-Pad38)") (class "Default")
      (node (ref "J2") (pin "38") (pinfunction "-DTR_MHX_38") (pintype "bidirectional"))
    )
    (net (code "32") (name "unconnected-(J2--FAULT-Pad25)") (class "Default")
      (node (ref "J2") (pin "25") (pinfunction "-FAULT_25") (pintype "bidirectional"))
    )
    (net (code "33") (name "unconnected-(J2--RESET-Pad29)") (class "Default")
      (node (ref "J2") (pin "29") (pinfunction "-RESET_29") (pintype "bidirectional"))
    )
    (net (code "34") (name "unconnected-(J2--RST_MHX-Pad34)") (class "Default")
      (node (ref "J2") (pin "34") (pinfunction "-RST_MHX_34") (pintype "bidirectional"))
    )
    (net (code "35") (name "unconnected-(J2--RTS_MHX-Pad36)") (class "Default")
      (node (ref "J2") (pin "36") (pinfunction "-RTS_MHX_36") (pintype "bidirectional"))
    )
    (net (code "36") (name "unconnected-(J2-OFF_VCC-Pad31)") (class "Default")
      (node (ref "J2") (pin "31") (pinfunction "OFF_VCC_31") (pintype "bidirectional"))
    )
    (net (code "37") (name "unconnected-(J2-P1.0-Pad68)") (class "Default")
      (node (ref "J2") (pin "68") (pinfunction "P1.0_68") (pintype "bidirectional"))
    )
    (net (code "38") (name "unconnected-(J2-P1.1-Pad67)") (class "Default")
      (node (ref "J2") (pin "67") (pinfunction "P1.1_67") (pintype "bidirectional"))
    )
    (net (code "39") (name "unconnected-(J2-P1.2-Pad66)") (class "Default")
      (node (ref "J2") (pin "66") (pinfunction "P1.2_66") (pintype "bidirectional"))
    )
    (net (code "40") (name "unconnected-(J2-P1.3-Pad65)") (class "Default")
      (node (ref "J2") (pin "65") (pinfunction "P1.3_65") (pintype "bidirectional"))
    )
    (net (code "41") (name "unconnected-(J2-P1.4-Pad64)") (class "Default")
      (node (ref "J2") (pin "64") (pinfunction "P1.4_64") (pintype "bidirectional"))
    )
    (net (code "42") (name "unconnected-(J2-P1.5-Pad63)") (class "Default")
      (node (ref "J2") (pin "63") (pinfunction "P1.5_63") (pintype "bidirectional"))
    )
    (net (code "43") (name "unconnected-(J2-P1.6-Pad62)") (class "Default")
      (node (ref "J2") (pin "62") (pinfunction "P1.6_62") (pintype "bidirectional"))
    )
    (net (code "44") (name "unconnected-(J2-P1.7-Pad61)") (class "Default")
      (node (ref "J2") (pin "61") (pinfunction "P1.7_61") (pintype "bidirectional"))
    )
    (net (code "45") (name "unconnected-(J2-P2.0-Pad76)") (class "Default")
      (node (ref "J2") (pin "76") (pinfunction "P2.0_76") (pintype "bidirectional"))
    )
    (net (code "46") (name "unconnected-(J2-P2.1-Pad75)") (class "Default")
      (node (ref "J2") (pin "75") (pinfunction "P2.1_75") (pintype "bidirectional"))
    )
    (net (code "47") (name "unconnected-(J2-P2.2-Pad74)") (class "Default")
      (node (ref "J2") (pin "74") (pinfunction "P2.2_74") (pintype "bidirectional"))
    )
    (net (code "48") (name "unconnected-(J2-P2.3-Pad73)") (class "Default")
      (node (ref "J2") (pin "73") (pinfunction "P2.3_73") (pintype "bidirectional"))
    )
    (net (code "49") (name "unconnected-(J2-P2.4-Pad72)") (class "Default")
      (node (ref "J2") (pin "72") (pinfunction "P2.4_72") (pintype "bidirectional"))
    )
    (net (code "50") (name "unconnected-(J2-P2.5-Pad71)") (class "Default")
      (node (ref "J2") (pin "71") (pinfunction "P2.5_71") (pintype "bidirectional"))
    )
    (net (code "51") (name "unconnected-(J2-P2.6-Pad70)") (class "Default")
      (node (ref "J2") (pin "70") (pinfunction "P2.6_70") (pintype "bidirectional"))
    )
    (net (code "52") (name "unconnected-(J2-P2.7-Pad69)") (class "Default")
      (node (ref "J2") (pin "69") (pinfunction "P2.7_69") (pintype "bidirectional"))
    )
    (net (code "53") (name "unconnected-(J2-P3.0-Pad24)") (class "Default")
      (node (ref "J2") (pin "24") (pinfunction "P3.0_24") (pintype "bidirectional"))
    )
    (net (code "54") (name "unconnected-(J2-P3.1-Pad23)") (class "Default")
      (node (ref "J2") (pin "23") (pinfunction "P3.1_23") (pintype "bidirectional"))
    )
    (net (code "55") (name "unconnected-(J2-P3.2-Pad22)") (class "Default")
      (node (ref "J2") (pin "22") (pinfunction "P3.2_22") (pintype "bidirectional"))
    )
    (net (code "56") (name "unconnected-(J2-P3.3-Pad21)") (class "Default")
      (node (ref "J2") (pin "21") (pinfunction "P3.3_21") (pintype "bidirectional"))
    )
    (net (code "57") (name "unconnected-(J2-P3.4-Pad20)") (class "Default")
      (node (ref "J2") (pin "20") (pinfunction "P3.4_20") (pintype "bidirectional"))
    )
    (net (code "58") (name "unconnected-(J2-P3.5-Pad19)") (class "Default")
      (node (ref "J2") (pin "19") (pinfunction "P3.5_19") (pintype "bidirectional"))
    )
    (net (code "59") (name "unconnected-(J2-P3.6-Pad18)") (class "Default")
      (node (ref "J2") (pin "18") (pinfunction "P3.6_18") (pintype "bidirectional"))
    )
    (net (code "60") (name "unconnected-(J2-P3.7-Pad17)") (class "Default")
      (node (ref "J2") (pin "17") (pinfunction "P3.7_17") (pintype "bidirectional"))
    )
    (net (code "61") (name "unconnected-(J2-P4.0-Pad16)") (class "Default")
      (node (ref "J2") (pin "16") (pinfunction "P4.0_16") (pintype "bidirectional"))
    )
    (net (code "62") (name "unconnected-(J2-P4.1-Pad15)") (class "Default")
      (node (ref "J2") (pin "15") (pinfunction "P4.1_15") (pintype "bidirectional"))
    )
    (net (code "63") (name "unconnected-(J2-P4.2-Pad14)") (class "Default")
      (node (ref "J2") (pin "14") (pinfunction "P4.2_14") (pintype "bidirectional"))
    )
    (net (code "64") (name "unconnected-(J2-P4.3-Pad13)") (class "Default")
      (node (ref "J2") (pin "13") (pinfunction "P4.3_13") (pintype "bidirectional"))
    )
    (net (code "65") (name "unconnected-(J2-P4.4-Pad12)") (class "Default")
      (node (ref "J2") (pin "12") (pinfunction "P4.4_12") (pintype "bidirectional"))
    )
    (net (code "66") (name "unconnected-(J2-P4.5-Pad11)") (class "Default")
      (node (ref "J2") (pin "11") (pinfunction "P4.5_11") (pintype "bidirectional"))
    )
    (net (code "67") (name "unconnected-(J2-P4.6-Pad10)") (class "Default")
      (node (ref "J2") (pin "10") (pinfunction "P4.6_10") (pintype "bidirectional"))
    )
    (net (code "68") (name "unconnected-(J2-P4.7-Pad9)") (class "Default")
      (node (ref "J2") (pin "9") (pinfunction "P4.7_9") (pintype "bidirectional"))
    )
    (net (code "69") (name "unconnected-(J2-P5.0-Pad8)") (class "Default")
      (node (ref "J2") (pin "8") (pinfunction "P5.0_8") (pintype "bidirectional"))
    )
    (net (code "70") (name "unconnected-(J2-P5.1-Pad7)") (class "Default")
      (node (ref "J2") (pin "7") (pinfunction "P5.1_7") (pintype "bidirectional"))
    )
    (net (code "71") (name "unconnected-(J2-P5.2-Pad6)") (class "Default")
      (node (ref "J2") (pin "6") (pinfunction "P5.2_6") (pintype "bidirectional"))
    )
    (net (code "72") (name "unconnected-(J2-P5.3-Pad5)") (class "Default")
      (node (ref "J2") (pin "5") (pinfunction "P5.3_5") (pintype "bidirectional"))
    )
    (net (code "73") (name "unconnected-(J2-P5.4-Pad4)") (class "Default")
      (node (ref "J2") (pin "4") (pinfunction "P5.4_4") (pintype "bidirectional"))
    )
    (net (code "74") (name "unconnected-(J2-P5.5-Pad3)") (class "Default")
      (node (ref "J2") (pin "3") (pinfunction "P5.5_3") (pintype "bidirectional"))
    )
    (net (code "75") (name "unconnected-(J2-P5.6-Pad2)") (class "Default")
      (node (ref "J2") (pin "2") (pinfunction "P5.6_2") (pintype "bidirectional"))
    )
    (net (code "76") (name "unconnected-(J2-P5.7-Pad1)") (class "Default")
      (node (ref "J2") (pin "1") (pinfunction "P5.7_1") (pintype "bidirectional"))
    )
    (net (code "77") (name "unconnected-(J2-P6.0-Pad60)") (class "Default")
      (node (ref "J2") (pin "60") (pinfunction "P6.0_60") (pintype "bidirectional"))
    )
    (net (code "78") (name "unconnected-(J2-P6.1-Pad59)") (class "Default")
      (node (ref "J2") (pin "59") (pinfunction "P6.1_59") (pintype "bidirectional"))
    )
    (net (code "79") (name "unconnected-(J2-P6.2-Pad58)") (class "Default")
      (node (ref "J2") (pin "58") (pinfunction "P6.2_58") (pintype "bidirectional"))
    )
    (net (code "80") (name "unconnected-(J2-P6.3-Pad57)") (class "Default")
      (node (ref "J2") (pin "57") (pinfunction "P6.3_57") (pintype "bidirectional"))
    )
    (net (code "81") (name "unconnected-(J2-P6.4-Pad56)") (class "Default")
      (node (ref "J2") (pin "56") (pinfunction "P6.4_56") (pintype "bidirectional"))
    )
    (net (code "82") (name "unconnected-(J2-P6.5-Pad55)") (class "Default")
      (node (ref "J2") (pin "55") (pinfunction "P6.5_55") (pintype "bidirectional"))
    )
    (net (code "83") (name "unconnected-(J2-P6.6-Pad54)") (class "Default")
      (node (ref "J2") (pin "54") (pinfunction "P6.6_54") (pintype "bidirectional"))
    )
    (net (code "84") (name "unconnected-(J2-P6.7-Pad53)") (class "Default")
      (node (ref "J2") (pin "53") (pinfunction "P6.7_53") (pintype "bidirectional"))
    )
    (net (code "85") (name "unconnected-(J2-RSVD0-Pad44)") (class "Default")
      (node (ref "J2") (pin "44") (pinfunction "RSVD0_44") (pintype "bidirectional"))
    )
    (net (code "86") (name "unconnected-(J2-RSVD1-Pad45)") (class "Default")
      (node (ref "J2") (pin "45") (pinfunction "RSVD1_45") (pintype "bidirectional"))
    )
    (net (code "87") (name "unconnected-(J2-RSVD2-Pad46)") (class "Default")
      (node (ref "J2") (pin "46") (pinfunction "RSVD2_46") (pintype "bidirectional"))
    )
    (net (code "88") (name "unconnected-(J2-RXD_MHX-Pad40)") (class "Default")
      (node (ref "J2") (pin "40") (pinfunction "RXD_MHX_40") (pintype "bidirectional"))
    )
    (net (code "89") (name "unconnected-(J2-SENSE-Pad27)") (class "Default")
      (node (ref "J2") (pin "27") (pinfunction "SENSE_27") (pintype "bidirectional"))
    )
    (net (code "90") (name "unconnected-(J2-SW0-Pad85)") (class "Default")
      (node (ref "J2") (pin "85") (pinfunction "SW0_85") (pintype "bidirectional"))
    )
    (net (code "91") (name "unconnected-(J2-SW0-Pad86)") (class "Default")
      (node (ref "J2") (pin "86") (pinfunction "SW0_86") (pintype "bidirectional"))
    )
    (net (code "92") (name "unconnected-(J2-SW1-Pad87)") (class "Default")
      (node (ref "J2") (pin "87") (pinfunction "SW1_87") (pintype "bidirectional"))
    )
    (net (code "93") (name "unconnected-(J2-SW1-Pad88)") (class "Default")
      (node (ref "J2") (pin "88") (pinfunction "SW1_88") (pintype "bidirectional"))
    )
    (net (code "94") (name "unconnected-(J2-SW2-Pad89)") (class "Default")
      (node (ref "J2") (pin "89") (pinfunction "SW2_89") (pintype "bidirectional"))
    )
    (net (code "95") (name "unconnected-(J2-SW2-Pad90)") (class "Default")
      (node (ref "J2") (pin "90") (pinfunction "SW2_90") (pintype "bidirectional"))
    )
    (net (code "96") (name "unconnected-(J2-SW3-Pad91)") (class "Default")
      (node (ref "J2") (pin "91") (pinfunction "SW3_91") (pintype "bidirectional"))
    )
    (net (code "97") (name "unconnected-(J2-SW3-Pad92)") (class "Default")
      (node (ref "J2") (pin "92") (pinfunction "SW3_92") (pintype "bidirectional"))
    )
    (net (code "98") (name "unconnected-(J2-SW4-Pad93)") (class "Default")
      (node (ref "J2") (pin "93") (pinfunction "SW4_93") (pintype "bidirectional"))
    )
    (net (code "99") (name "unconnected-(J2-SW4-Pad94)") (class "Default")
      (node (ref "J2") (pin "94") (pinfunction "SW4_94") (pintype "bidirectional"))
    )
    (net (code "100") (name "unconnected-(J2-SW5-Pad95)") (class "Default")
      (node (ref "J2") (pin "95") (pinfunction "SW5_95") (pintype "bidirectional"))
    )
    (net (code "101") (name "unconnected-(J2-SW5-Pad96)") (class "Default")
      (node (ref "J2") (pin "96") (pinfunction "SW5_96") (pintype "bidirectional"))
    )
    (net (code "102") (name "unconnected-(J2-TXD_MHX-Pad39)") (class "Default")
      (node (ref "J2") (pin "39") (pinfunction "TXD_MHX_39") (pintype "bidirectional"))
    )
    (net (code "103") (name "unconnected-(J2-USER0-Pad47)") (class "Default")
      (node (ref "J2") (pin "47") (pinfunction "USER0_47") (pintype "bidirectional"))
    )
    (net (code "104") (name "unconnected-(J2-USER1-Pad48)") (class "Default")
      (node (ref "J2") (pin "48") (pinfunction "USER1_48") (pintype "bidirectional"))
    )
    (net (code "105") (name "unconnected-(J2-USER2-Pad49)") (class "Default")
      (node (ref "J2") (pin "49") (pinfunction "USER2_49") (pintype "bidirectional"))
    )
    (net (code "106") (name "unconnected-(J2-USER3-Pad50)") (class "Default")
      (node (ref "J2") (pin "50") (pinfunction "USER3_50") (pintype "bidirectional"))
    )
    (net (code "107") (name "unconnected-(J2-USER4-Pad51)") (class "Default")
      (node (ref "J2") (pin "51") (pinfunction "USER4_51") (pintype "bidirectional"))
    )
    (net (code "108") (name "unconnected-(J2-USER5-Pad52)") (class "Default")
      (node (ref "J2") (pin "52") (pinfunction "USER5_52") (pintype "bidirectional"))
    )
    (net (code "109") (name "unconnected-(J2-USER6-Pad99)") (class "Default")
      (node (ref "J2") (pin "99") (pinfunction "USER6_99") (pintype "bidirectional"))
    )
    (net (code "110") (name "unconnected-(J2-USER7-Pad100)") (class "Default")
      (node (ref "J2") (pin "100") (pinfunction "USER7_100") (pintype "bidirectional"))
    )
    (net (code "111") (name "unconnected-(J2-USER8-Pad101)") (class "Default")
      (node (ref "J2") (pin "101") (pinfunction "USER8_101") (pintype "bidirectional"))
    )
    (net (code "112") (name "unconnected-(J2-USER9-Pad102)") (class "Default")
      (node (ref "J2") (pin "102") (pinfunction "USER9_102") (pintype "bidirectional"))
    )
    (net (code "113") (name "unconnected-(J2-USER10-Pad103)") (class "Default")
      (node (ref "J2") (pin "103") (pinfunction "USER10_103") (pintype "bidirectional"))
    )
    (net (code "114") (name "unconnected-(J2-USER11-Pad104)") (class "Default")
      (node (ref "J2") (pin "104") (pinfunction "USER11_104") (pintype "bidirectional"))
    )
    (net (code "115") (name "unconnected-(J2-VBACKUP-Pad42)") (class "Default")
      (node (ref "J2") (pin "42") (pinfunction "VBACKUP_42") (pintype "bidirectional"))
    )
    (net (code "116") (name "unconnected-(J2-VCC_SYS-Pad79)") (class "Default")
      (node (ref "J2") (pin "79") (pinfunction "VCC_SYS_79") (pintype "bidirectional"))
    )
    (net (code "117") (name "unconnected-(J2-VCC_SYS-Pad80)") (class "Default")
      (node (ref "J2") (pin "80") (pinfunction "VCC_SYS_80") (pintype "bidirectional"))
    )
    (net (code "118") (name "unconnected-(J2-VEREF+-Pad28)") (class "Default")
      (node (ref "J2") (pin "28") (pinfunction "VEREF+_28") (pintype "bidirectional"))
    )
    (net (code "119") (name "unconnected-(J2-VREF+-Pad26)") (class "Default")
      (node (ref "J2") (pin "26") (pinfunction "VREF+_26") (pintype "bidirectional"))
    )
    (net (code "120") (name "unconnected-(J2-VREF--Pad30)") (class "Default")
      (node (ref "J2") (pin "30") (pinfunction "VREF-_30") (pintype "bidirectional"))
    )
    (net (code "121") (name "unconnected-(OK1-A1-Pad1)") (class "Default")
      (node (ref "OK1") (pin "1") (pinfunction "A1_1") (pintype "bidirectional"))
    )
    (net (code "122") (name "unconnected-(OK1-A2-Pad3)") (class "Default")
      (node (ref "OK1") (pin "3") (pinfunction "A2_3") (pintype "bidirectional"))
    )
    (net (code "123") (name "unconnected-(OK1-A3-Pad5)") (class "Default")
      (node (ref "OK1") (pin "5") (pinfunction "A3_5") (pintype "bidirectional"))
    )
    (net (code "124") (name "unconnected-(OK1-A4-Pad7)") (class "Default")
      (node (ref "OK1") (pin "7") (pinfunction "A4_7") (pintype "bidirectional"))
    )
    (net (code "125") (name "unconnected-(OK1-C1-Pad16)") (class "Default")
      (node (ref "OK1") (pin "16") (pinfunction "C1_16") (pintype "bidirectional"))
    )
    (net (code "126") (name "unconnected-(OK1-C2-Pad14)") (class "Default")
      (node (ref "OK1") (pin "14") (pinfunction "C2_14") (pintype "bidirectional"))
    )
    (net (code "127") (name "unconnected-(OK1-C3-Pad12)") (class "Default")
      (node (ref "OK1") (pin "12") (pinfunction "C3_12") (pintype "bidirectional"))
    )
    (net (code "128") (name "unconnected-(OK1-C4-Pad10)") (class "Default")
      (node (ref "OK1") (pin "10") (pinfunction "C4_10") (pintype "bidirectional"))
    )
    (net (code "129") (name "unconnected-(OK1-E1-Pad15)") (class "Default")
      (node (ref "OK1") (pin "15") (pinfunction "E1_15") (pintype "bidirectional"))
    )
    (net (code "130") (name "unconnected-(OK1-E2-Pad13)") (class "Default")
      (node (ref "OK1") (pin "13") (pinfunction "E2_13") (pintype "bidirectional"))
    )
    (net (code "131") (name "unconnected-(OK1-E3-Pad11)") (class "Default")
      (node (ref "OK1") (pin "11") (pinfunction "E3_11") (pintype "bidirectional"))
    )
    (net (code "132") (name "unconnected-(OK1-E4-Pad9)") (class "Default")
      (node (ref "OK1") (pin "9") (pinfunction "E4_9") (pintype "bidirectional"))
    )
    (net (code "133") (name "unconnected-(U1-ADC_IN0-Pad2)") (class "Default")
      (node (ref "U1") (pin "2") (pinfunction "ADC_IN0_2") (pintype "bidirectional"))
    )
    (net (code "134") (name "unconnected-(U1-ADC_IN1-Pad1)") (class "Default")
      (node (ref "U1") (pin "1") (pinfunction "ADC_IN1_1") (pintype "bidirectional"))
    )
    (net (code "135") (name "unconnected-(U1-ADC_IN2-Pad4)") (class "Default")
      (node (ref "U1") (pin "4") (pinfunction "ADC_IN2_4") (pintype "bidirectional"))
    )
    (net (code "136") (name "unconnected-(U1-ADC_IN3-Pad3)") (class "Default")
      (node (ref "U1") (pin "3") (pinfunction "ADC_IN3_3") (pintype "bidirectional"))
    )
    (net (code "137") (name "unconnected-(U1-ADC_IN4-Pad6)") (class "Default")
      (node (ref "U1") (pin "6") (pinfunction "ADC_IN4_6") (pintype "bidirectional"))
    )
    (net (code "138") (name "unconnected-(U1-ADC_IN7-Pad5)") (class "Default")
      (node (ref "U1") (pin "5") (pinfunction "ADC_IN7_5") (pintype "bidirectional"))
    )
    (net (code "139") (name "unconnected-(U1-AGND-Pad8)") (class "Default")
      (node (ref "U1") (pin "8") (pinfunction "AGND_8") (pintype "bidirectional"))
    )
    (net (code "140") (name "unconnected-(U1-CAN1_RX-Pad20)") (class "Default")
      (node (ref "U1") (pin "20") (pinfunction "CAN1_RX_20") (pintype "bidirectional"))
    )
    (net (code "141") (name "unconnected-(U1-CAN1_TX-Pad22)") (class "Default")
      (node (ref "U1") (pin "22") (pinfunction "CAN1_TX_22") (pintype "bidirectional"))
    )
    (net (code "142") (name "unconnected-(U1-ERX_JM-Pad44)") (class "Default")
      (node (ref "U1") (pin "44") (pinfunction "ERX_JM_44") (pintype "bidirectional"))
    )
    (net (code "143") (name "unconnected-(U1-ERX_JP-Pad43)") (class "Default")
      (node (ref "U1") (pin "43") (pinfunction "ERX_JP_43") (pintype "bidirectional"))
    )
    (net (code "144") (name "unconnected-(U1-ETX_JM-Pad46)") (class "Default")
      (node (ref "U1") (pin "46") (pinfunction "ETX_JM_46") (pintype "bidirectional"))
    )
    (net (code "145") (name "unconnected-(U1-ETX_JP-Pad45)") (class "Default")
      (node (ref "U1") (pin "45") (pinfunction "ETX_JP_45") (pintype "bidirectional"))
    )
    (net (code "146") (name "unconnected-(U1-GND-Pad18)") (class "Default")
      (node (ref "U1") (pin "18") (pinfunction "GND_18") (pintype "bidirectional"))
    )
    (net (code "147") (name "unconnected-(U1-IRQ2-Pad50)") (class "Default")
      (node (ref "U1") (pin "50") (pinfunction "IRQ2_50") (pintype "bidirectional"))
    )
    (net (code "148") (name "unconnected-(U1-IRQ3-Pad49)") (class "Default")
      (node (ref "U1") (pin "49") (pinfunction "IRQ3_49") (pintype "bidirectional"))
    )
    (net (code "149") (name "unconnected-(U1-IRQ7-Pad9)") (class "Default")
      (node (ref "U1") (pin "9") (pinfunction "IRQ7_9") (pintype "bidirectional"))
    )
    (net (code "150") (name "unconnected-(U1-LINKLED-Pad42)") (class "Default")
      (node (ref "U1") (pin "42") (pinfunction "LINKLED_42") (pintype "bidirectional"))
    )
    (net (code "151") (name "unconnected-(U1-OW_DAT-Pad12)") (class "Default")
      (node (ref "U1") (pin "12") (pinfunction "OW_DAT_12") (pintype "bidirectional"))
    )
    (net (code "152") (name "unconnected-(U1-RSTI-Pad11)") (class "Default")
      (node (ref "U1") (pin "11") (pinfunction "RSTI_11") (pintype "bidirectional"))
    )
    (net (code "153") (name "unconnected-(U1-SDHC_CLK-Pad31)") (class "Default")
      (node (ref "U1") (pin "31") (pinfunction "SDHC_CLK_31") (pintype "bidirectional"))
    )
    (net (code "154") (name "unconnected-(U1-SDHC_CMD-Pad33)") (class "Default")
      (node (ref "U1") (pin "33") (pinfunction "SDHC_CMD_33") (pintype "bidirectional"))
    )
    (net (code "155") (name "unconnected-(U1-SDHC_DAT0-Pad35)") (class "Default")
      (node (ref "U1") (pin "35") (pinfunction "SDHC_DAT0_35") (pintype "bidirectional"))
    )
    (net (code "156") (name "unconnected-(U1-SDHC_DAT1-Pad37)") (class "Default")
      (node (ref "U1") (pin "37") (pinfunction "SDHC_DAT1_37") (pintype "bidirectional"))
    )
    (net (code "157") (name "unconnected-(U1-SDHC_DAT2-Pad39)") (class "Default")
      (node (ref "U1") (pin "39") (pinfunction "SDHC_DAT2_39") (pintype "bidirectional"))
    )
    (net (code "158") (name "unconnected-(U1-SDHC_DAT3-Pad15)") (class "Default")
      (node (ref "U1") (pin "15") (pinfunction "SDHC_DAT3_15") (pintype "bidirectional"))
    )
    (net (code "159") (name "unconnected-(U1-SPEEDLED-Pad40)") (class "Default")
      (node (ref "U1") (pin "40") (pinfunction "SPEEDLED_40") (pintype "bidirectional"))
    )
    (net (code "160") (name "unconnected-(U1-T0IN-Pad19)") (class "Default")
      (node (ref "U1") (pin "19") (pinfunction "T0IN_19") (pintype "bidirectional"))
    )
    (net (code "161") (name "unconnected-(U1-T1IN-Pad21)") (class "Default")
      (node (ref "U1") (pin "21") (pinfunction "T1IN_21") (pintype "bidirectional"))
    )
    (net (code "162") (name "unconnected-(U1-T2IN-Pad23)") (class "Default")
      (node (ref "U1") (pin "23") (pinfunction "T2IN_23") (pintype "bidirectional"))
    )
    (net (code "163") (name "unconnected-(U1-T3IN-Pad25)") (class "Default")
      (node (ref "U1") (pin "25") (pinfunction "T3IN_25") (pintype "bidirectional"))
    )
    (net (code "164") (name "unconnected-(U1-UART0_CTS-Pad30)") (class "Default")
      (node (ref "U1") (pin "30") (pinfunction "UART0_CTS_30") (pintype "bidirectional"))
    )
    (net (code "165") (name "unconnected-(U1-UART0_RTS-Pad28)") (class "Default")
      (node (ref "U1") (pin "28") (pinfunction "UART0_RTS_28") (pintype "bidirectional"))
    )
    (net (code "166") (name "unconnected-(U1-UART0_RX-Pad24)") (class "Default")
      (node (ref "U1") (pin "24") (pinfunction "UART0_RX_24") (pintype "bidirectional"))
    )
    (net (code "167") (name "unconnected-(U1-UART0_TX-Pad26)") (class "Default")
      (node (ref "U1") (pin "26") (pinfunction "UART0_TX_26") (pintype "bidirectional"))
    )
    (net (code "168") (name "unconnected-(U1-UART1_CTS-Pad38)") (class "Default")
      (node (ref "U1") (pin "38") (pinfunction "UART1_CTS_38") (pintype "bidirectional"))
    )
    (net (code "169") (name "unconnected-(U1-UART1_RTS-Pad36)") (class "Default")
      (node (ref "U1") (pin "36") (pinfunction "UART1_RTS_36") (pintype "bidirectional"))
    )
    (net (code "170") (name "unconnected-(U1-UART1_RX-Pad32)") (class "Default")
      (node (ref "U1") (pin "32") (pinfunction "UART1_RX_32") (pintype "bidirectional"))
    )
    (net (code "171") (name "unconnected-(U1-UART1_TX-Pad34)") (class "Default")
      (node (ref "U1") (pin "34") (pinfunction "UART1_TX_34") (pintype "bidirectional"))
    )
    (net (code "172") (name "unconnected-(U1-UART2_CTS-Pad10)") (class "Default")
      (node (ref "U1") (pin "10") (pinfunction "UART2_CTS_10") (pintype "bidirectional"))
    )
    (net (code "173") (name "unconnected-(U1-UART2_RTS-Pad14)") (class "Default")
      (node (ref "U1") (pin "14") (pinfunction "UART2_RTS_14") (pintype "bidirectional"))
    )
    (net (code "174") (name "unconnected-(U1-UART2_RX-Pad13)") (class "Default")
      (node (ref "U1") (pin "13") (pinfunction "UART2_RX_13") (pintype "bidirectional"))
    )
    (net (code "175") (name "unconnected-(U1-UART2_TX-Pad16)") (class "Default")
      (node (ref "U1") (pin "16") (pinfunction "UART2_TX_16") (pintype "bidirectional"))
    )
    (net (code "176") (name "unconnected-(U1-USBO_DM-Pad51)") (class "Default")
      (node (ref "U1") (pin "51") (pinfunction "USBO_DM_51") (pintype "bidirectional"))
    )
    (net (code "177") (name "unconnected-(U1-USBO_DP-Pad52)") (class "Default")
      (node (ref "U1") (pin "52") (pinfunction "USBO_DP_52") (pintype "bidirectional"))
    )
    (net (code "178") (name "unconnected-(U1-VCC3VE-Pad41)") (class "Default")
      (node (ref "U1") (pin "41") (pinfunction "VCC3VE_41") (pintype "bidirectional"))
    )
    (net (code "179") (name "unconnected-(U1-VDDA_DAC_ADC-Pad7)") (class "Default")
      (node (ref "U1") (pin "7") (pinfunction "VDDA_DAC_ADC_7") (pintype "bidirectional"))
    )
    (net (code "180") (name "unconnected-(U2-COMP-PadB7)") (class "Default")
      (node (ref "U2") (pin "B7") (pinfunction "COMP_B7") (pintype "bidirectional"))
    )
    (net (code "181") (name "unconnected-(U2-EXTV_CC-PadF6)") (class "Default")
      (node (ref "U2") (pin "F6") (pinfunction "EXTV_CC_F6") (pintype "bidirectional"))
    )
    (net (code "182") (name "unconnected-(U2-PLLIN-PadB9)") (class "Default")
      (node (ref "U2") (pin "B9") (pinfunction "PLLIN_B9") (pintype "bidirectional"))
    )
    (net (code "183") (name "unconnected-(U2-SS-PadA6)") (class "Default")
      (node (ref "U2") (pin "A6") (pinfunction "SS_A6") (pintype "bidirectional"))
    )
    (net (code "184") (name "unconnected-(U2-STBYMD-PadA10)") (class "Default")
      (node (ref "U2") (pin "A10") (pinfunction "STBYMD_A10") (pintype "bidirectional"))
    )
  )
)
